# Boris_IO_2.net
KiCad netlist of a schematic drawn in Altium Designer
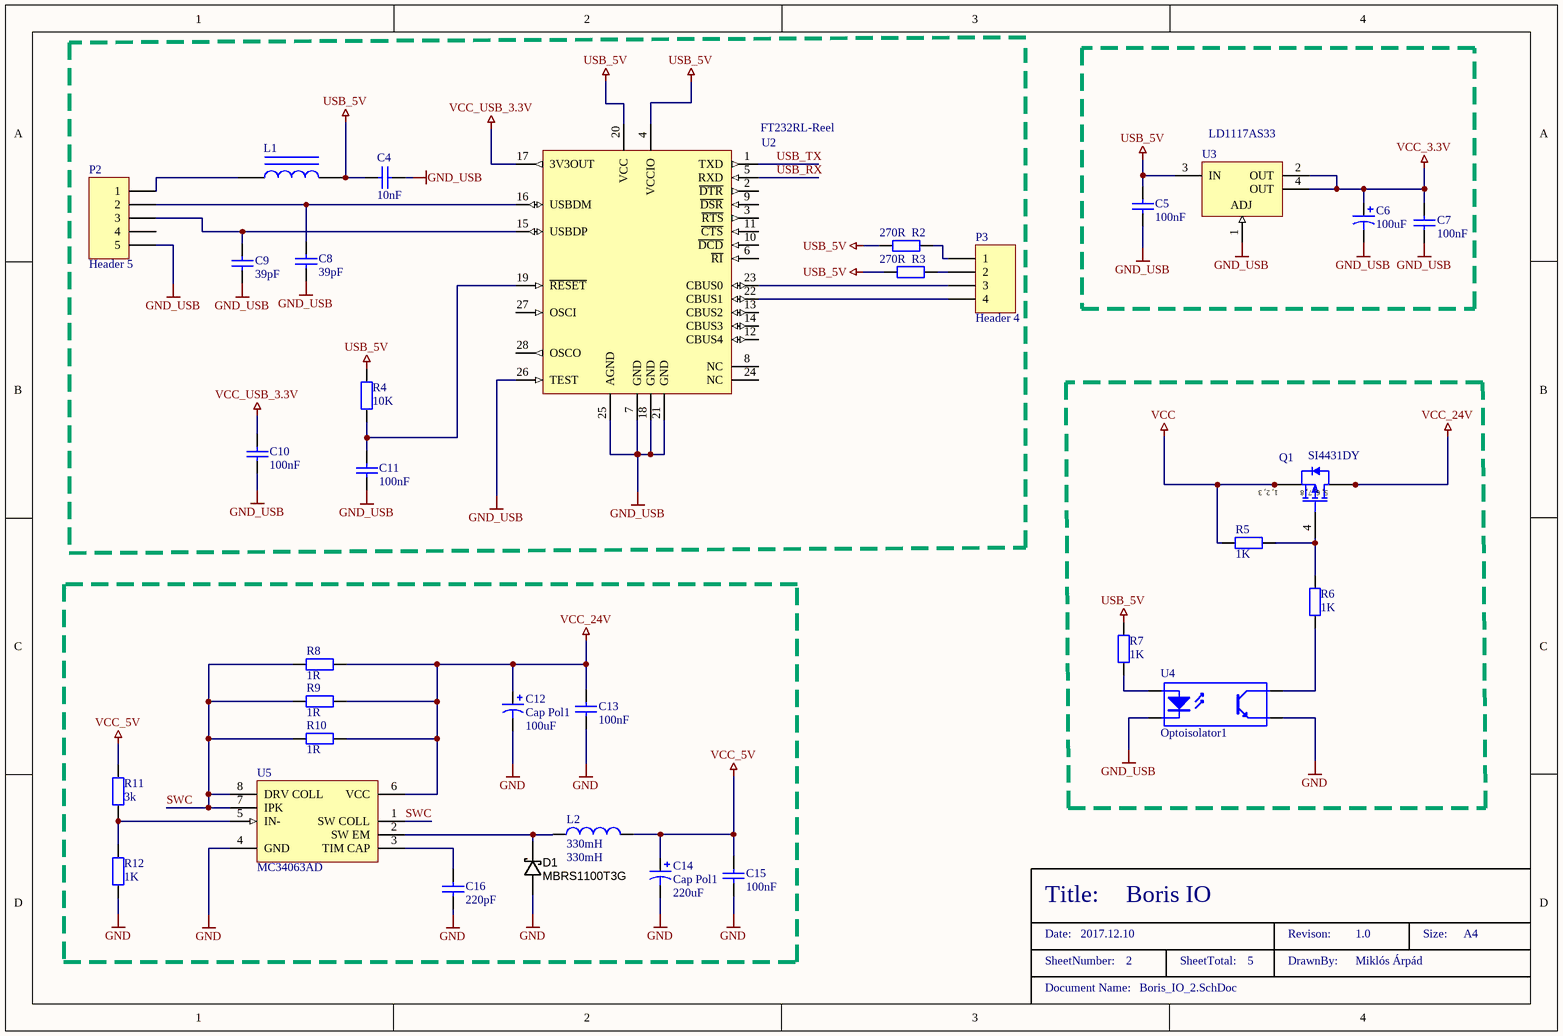
[diagram p0: Boris_IO_2.SchDoc]

(export (version "E")
  (design (tool "Eeschema 10.0.6"))
  (components
    (comp (ref "C4")
      (value "10nF")
      (footprint "0805_CAP")
      (description "Capacitor")
      (libsource (lib "Miscellaneous Devices") (part "Cap"))
    )
    (comp (ref "C5")
      (value "100nF")
      (footprint "0805_CAP")
      (description "Capacitor")
      (libsource (lib "Miscellaneous Devices") (part "Cap"))
    )
    (comp (ref "C6")
      (value "100uF")
      (footprint "7343")
      (description "Polarized Capacitor (Radial)")
      (libsource (lib "MI_SPAZIO") (part "Cap Pol1"))
    )
    (comp (ref "C7")
      (value "100nF")
      (footprint "0805_CAP")
      (description "Capacitor")
      (libsource (lib "Miscellaneous Devices") (part "Cap"))
    )
    (comp (ref "C8")
      (value "39pF")
      (footprint "0805_CAP")
      (description "Capacitor")
      (libsource (lib "Miscellaneous Devices") (part "Cap"))
    )
    (comp (ref "C9")
      (value "39pF")
      (footprint "0805_CAP")
      (description "Capacitor")
      (libsource (lib "Miscellaneous Devices") (part "Cap"))
    )
    (comp (ref "C10")
      (value "100nF")
      (footprint "0805_CAP")
      (description "Capacitor")
      (libsource (lib "Miscellaneous Devices") (part "Cap"))
    )
    (comp (ref "C11")
      (value "100nF")
      (footprint "0805_CAP")
      (description "Capacitor")
      (libsource (lib "Miscellaneous Devices") (part "Cap"))
    )
    (comp (ref "C12")
      (value "Cap Pol1")
      (footprint "CAP_ELEC_SIZE_G")
      (description "Polarized Capacitor (Radial)")
      (fields (field (name "ALTIUM_VALUE") "100uF"))
      (libsource (lib "Miscellaneous Devices") (part "Cap Pol1"))
    )
    (comp (ref "C13")
      (value "100nF")
      (footprint "CAPC3216N")
      (description "Capacitor")
      (libsource (lib "Miscellaneous Devices") (part "Cap"))
    )
    (comp (ref "C14")
      (value "Cap Pol1")
      (footprint "CAP_ELEC_SIZE_E")
      (description "Polarized Capacitor (Radial)")
      (fields (field (name "ALTIUM_VALUE") "220uF"))
      (libsource (lib "Miscellaneous Devices") (part "Cap Pol1"))
    )
    (comp (ref "C15")
      (value "100nF")
      (footprint "CAPC3216N")
      (description "Capacitor")
      (libsource (lib "Miscellaneous Devices") (part "Cap"))
    )
    (comp (ref "C16")
      (value "220pF")
      (footprint "0805_CAP")
      (description "Capacitor")
      (libsource (lib "Miscellaneous Devices") (part "Cap"))
    )
    (comp (ref "D1")
      (value "MBRS1100T3G")
      (footprint "DO-214AA")
      (description "Diode Schottky SMD 30V 1A DO-214AA")
      (libsource (lib "PBL - Diodes") (part "DIODE_SCHOTTKY_MBRS130L"))
    )
    (comp (ref "L1")
      (value "Inductor Iron")
      (footprint "0805_ind")
      (description "Magnetic-Core Inductor")
      (libsource (lib "Miscellaneous Devices") (part "Inductor Iron"))
    )
    (comp (ref "L2")
      (value "330mH")
      (footprint "IND_Coilcraft_DO3316P_SM")
      (description "Inductor")
      (fields (field (name "ALTIUM_VALUE") "330mH"))
      (libsource (lib "Miscellaneous Devices") (part "Inductor"))
    )
    (comp (ref "P2")
      (value "Header 5")
      (footprint "HDR1X5")
      (description "Header, 5-Pin")
      (fields (field (name "PUBLISHER") "Altium Limited"))
      (libsource (lib "Miscellaneous Connectors") (part "Header 5"))
    )
    (comp (ref "P3")
      (value "Header 4")
      (footprint "HDR1X4")
      (description "Header, 4-Pin")
      (fields (field (name "PUBLISHER") "Altium Limited"))
      (libsource (lib "Miscellaneous Connectors") (part "Header 4"))
    )
    (comp (ref "Q1")
      (value "SI4431DY")
      (footprint "SO-8_N")
      (description "P-Channel 30V (D-S)  MOSFET")
      (fields (field (name "PUBLISHER") "Altium Limited"))
      (libsource (lib "Vishay Siliconix Discrete MOSFET") (part "SI4431DY"))
    )
    (comp (ref "R2")
      (value "270R")
      (footprint "0805_RES")
      (description "Resistor")
      (libsource (lib "") (part "Res2_2"))
    )
    (comp (ref "R3")
      (value "270R")
      (footprint "0805_RES")
      (description "Resistor")
      (libsource (lib "") (part "Res2_2"))
    )
    (comp (ref "R4")
      (value "10K")
      (footprint "0805_RES")
      (description "Resistor")
      (libsource (lib "") (part "Res2_3"))
    )
    (comp (ref "R5")
      (value "1K")
      (footprint "RESC3216N")
      (description "Resistor")
      (libsource (lib "") (part "Res2_2"))
    )
    (comp (ref "R6")
      (value "1K")
      (footprint "RESC3216N")
      (description "Resistor")
      (libsource (lib "") (part "Res2_1"))
    )
    (comp (ref "R7")
      (value "1K")
      (footprint "RESC3216N")
      (description "Resistor")
      (libsource (lib "") (part "Res2_1"))
    )
    (comp (ref "R8")
      (value "1R")
      (footprint "RESC3216N")
      (description "Resistor")
      (libsource (lib "Miscellaneous Devices") (part "Res2"))
    )
    (comp (ref "R9")
      (value "1R")
      (footprint "RESC3216N")
      (description "Resistor")
      (libsource (lib "Miscellaneous Devices") (part "Res2"))
    )
    (comp (ref "R10")
      (value "1R")
      (footprint "RESC3216N")
      (description "Resistor")
      (libsource (lib "Miscellaneous Devices") (part "Res2"))
    )
    (comp (ref "R11")
      (value "3k")
      (footprint "RESC3216N")
      (description "Resistor")
      (libsource (lib "") (part "Res2_1"))
    )
    (comp (ref "R12")
      (value "1K")
      (footprint "RESC3216N")
      (description "Resistor")
      (libsource (lib "") (part "Res2_1"))
    )
    (comp (ref "U2")
      (value "FT232RL-Reel")
      (footprint "SSOP-28_N")
      (description "USB UART Asynchronous Serial Data Transfer Chip, SSOP-28, Tape and Reel")
      (libsource (lib "FTDI Communication UART") (part "FT232RL-Reel"))
    )
    (comp (ref "U3")
      (value "LD1117AS33")
      (footprint "318E-04")
      (description "Three-Terminal Adjustable Output Positive Voltage Regulator")
      (libsource (lib "ON Semi Power Mgt Voltage Regulator") (part "LM317MBSTT3"))
    )
    (comp (ref "U4")
      (value "Optoisolator1")
      (footprint "DIP-4")
      (description "4-Pin Phototransistor Optocoupler")
      (fields (field (name "PUBLISHER") "Altium Limited"))
      (libsource (lib "Miscellaneous Devices") (part "Optoisolator1"))
    )
    (comp (ref "U5")
      (value "MC34063AD")
      (footprint "751-05_N")
      (description "DC-to-DC Converter Control Circuit")
      (libsource (lib "ON Semi Power Mgt DC-DC Converter") (part "MC34063AD"))
    )
  )
  (nets
    (net (code "1") (name "/SWC") (class "Default")
      (node (ref "R10") (pin "2") (pinfunction "2_2") (pintype "passive"))
      (node (ref "R8") (pin "2") (pinfunction "2_2") (pintype "passive"))
      (node (ref "R9") (pin "2") (pinfunction "2_2") (pintype "passive"))
      (node (ref "U5") (pin "1") (pinfunction "SW_COLL_1") (pintype "passive"))
      (node (ref "U5") (pin "7") (pinfunction "IPK_7") (pintype "passive"))
      (node (ref "U5") (pin "8") (pinfunction "DRV_COLL_8") (pintype "open_collector"))
    )
    (net (code "2") (name "/USB_RX") (class "Default")
      (node (ref "U2") (pin "5") (pinfunction "RXD_5") (pintype "input"))
    )
    (net (code "3") (name "/USB_TX") (class "Default")
      (node (ref "U2") (pin "1") (pinfunction "TXD_1") (pintype "output"))
    )
    (net (code "4") (name "GND") (class "Default")
      (node (ref "C12") (pin "2") (pinfunction "2_2") (pintype "passive"))
      (node (ref "C13") (pin "2") (pinfunction "2_2") (pintype "passive"))
      (node (ref "C14") (pin "2") (pinfunction "2_2") (pintype "passive"))
      (node (ref "C15") (pin "2") (pinfunction "2_2") (pintype "passive"))
      (node (ref "C16") (pin "2") (pinfunction "2_2") (pintype "passive"))
      (node (ref "D1") (pin "A") (pinfunction "A_A") (pintype "passive"))
      (node (ref "R12") (pin "2") (pinfunction "2_2") (pintype "passive"))
      (node (ref "U4") (pin "3") (pinfunction "E_3") (pintype "passive"))
      (node (ref "U5") (pin "4") (pinfunction "GND_4") (pintype "power_in"))
    )
    (net (code "5") (name "GND_USB") (class "Default")
      (node (ref "C10") (pin "2") (pinfunction "2_2") (pintype "passive"))
      (node (ref "C11") (pin "2") (pinfunction "2_2") (pintype "passive"))
      (node (ref "C4") (pin "2") (pinfunction "2_2") (pintype "passive"))
      (node (ref "C5") (pin "2") (pinfunction "2_2") (pintype "passive"))
      (node (ref "C6") (pin "2") (pinfunction "2_2") (pintype "passive"))
      (node (ref "C7") (pin "2") (pinfunction "2_2") (pintype "passive"))
      (node (ref "C8") (pin "1") (pinfunction "1_1") (pintype "passive"))
      (node (ref "C9") (pin "1") (pinfunction "1_1") (pintype "passive"))
      (node (ref "P2") (pin "5") (pinfunction "5_5") (pintype "passive"))
      (node (ref "U2") (pin "18") (pinfunction "GND_18") (pintype "power_in"))
      (node (ref "U2") (pin "21") (pinfunction "GND_21") (pintype "power_in"))
      (node (ref "U2") (pin "25") (pinfunction "AGND_25") (pintype "power_in"))
      (node (ref "U2") (pin "26") (pinfunction "TEST_26") (pintype "input"))
      (node (ref "U2") (pin "7") (pinfunction "GND_7") (pintype "power_in"))
      (node (ref "U3") (pin "1") (pinfunction "ADJ_1") (pintype "input"))
      (node (ref "U4") (pin "2") (pinfunction "K_2") (pintype "passive"))
    )
    (net (code "6") (name "Net-(L1-Pad1)") (class "Default")
      (node (ref "L1") (pin "1") (pinfunction "1_1") (pintype "passive"))
      (node (ref "P2") (pin "1") (pinfunction "1_1") (pintype "passive"))
    )
    (net (code "7") (name "Net-(P3-Pad1)") (class "Default")
      (node (ref "P3") (pin "1") (pinfunction "1_1") (pintype "passive"))
      (node (ref "R2") (pin "2") (pinfunction "2_2") (pintype "passive"))
    )
    (net (code "8") (name "Net-(P3-Pad2)") (class "Default")
      (node (ref "P3") (pin "2") (pinfunction "2_2") (pintype "passive"))
      (node (ref "R3") (pin "2") (pinfunction "2_2") (pintype "passive"))
    )
    (net (code "9") (name "Net-(Q1-G)") (class "Default")
      (node (ref "Q1") (pin "4") (pinfunction "G_4") (pintype "passive"))
      (node (ref "R5") (pin "2") (pinfunction "2_2") (pintype "passive"))
      (node (ref "R6") (pin "1") (pinfunction "1_1") (pintype "passive"))
    )
    (net (code "10") (name "Net-(U2-CBUS0)") (class "Default")
      (node (ref "P3") (pin "3") (pinfunction "3_3") (pintype "passive"))
      (node (ref "U2") (pin "23") (pinfunction "CBUS0_23") (pintype "bidirectional"))
    )
    (net (code "11") (name "Net-(U2-CBUS1)") (class "Default")
      (node (ref "P3") (pin "4") (pinfunction "4_4") (pintype "passive"))
      (node (ref "U2") (pin "22") (pinfunction "CBUS1_22") (pintype "bidirectional"))
    )
    (net (code "12") (name "Net-(U2-USBDM)") (class "Default")
      (node (ref "C8") (pin "2") (pinfunction "2_2") (pintype "passive"))
      (node (ref "P2") (pin "2") (pinfunction "2_2") (pintype "passive"))
      (node (ref "U2") (pin "16") (pinfunction "USBDM_16") (pintype "bidirectional"))
    )
    (net (code "13") (name "Net-(U2-USBDP)") (class "Default")
      (node (ref "C9") (pin "2") (pinfunction "2_2") (pintype "passive"))
      (node (ref "P2") (pin "3") (pinfunction "3_3") (pintype "passive"))
      (node (ref "U2") (pin "15") (pinfunction "USBDP_15") (pintype "bidirectional"))
    )
    (net (code "14") (name "Net-(U2-~{RESET})") (class "Default")
      (node (ref "C11") (pin "1") (pinfunction "1_1") (pintype "passive"))
      (node (ref "R4") (pin "1") (pinfunction "1_1") (pintype "passive"))
      (node (ref "U2") (pin "19") (pinfunction "~{RESET}_19") (pintype "input"))
    )
    (net (code "15") (name "Net-(U4-A)") (class "Default")
      (node (ref "R7") (pin "2") (pinfunction "2_2") (pintype "passive"))
      (node (ref "U4") (pin "1") (pinfunction "A_1") (pintype "passive"))
    )
    (net (code "16") (name "Net-(U4-C)") (class "Default")
      (node (ref "R6") (pin "2") (pinfunction "2_2") (pintype "passive"))
      (node (ref "U4") (pin "4") (pinfunction "C_4") (pintype "passive"))
    )
    (net (code "17") (name "Net-(U5-IN-)") (class "Default")
      (node (ref "R11") (pin "2") (pinfunction "2_2") (pintype "passive"))
      (node (ref "R12") (pin "1") (pinfunction "1_1") (pintype "passive"))
      (node (ref "U5") (pin "5") (pinfunction "IN-_5") (pintype "input"))
    )
    (net (code "18") (name "Net-(U5-SW_EM)") (class "Default")
      (node (ref "D1") (pin "K") (pinfunction "K_K") (pintype "passive"))
      (node (ref "L2") (pin "1") (pinfunction "1_1") (pintype "passive"))
      (node (ref "U5") (pin "2") (pinfunction "SW_EM_2") (pintype "passive"))
    )
    (net (code "19") (name "Net-(U5-TIM_CAP)") (class "Default")
      (node (ref "C16") (pin "1") (pinfunction "1_1") (pintype "passive"))
      (node (ref "U5") (pin "3") (pinfunction "TIM_CAP_3") (pintype "passive"))
    )
    (net (code "20") (name "USB_5V") (class "Default")
      (node (ref "C4") (pin "1") (pinfunction "1_1") (pintype "passive"))
      (node (ref "C5") (pin "1") (pinfunction "1_1") (pintype "passive"))
      (node (ref "L1") (pin "2") (pinfunction "2_2") (pintype "passive"))
      (node (ref "R2") (pin "1") (pinfunction "1_1") (pintype "passive"))
      (node (ref "R3") (pin "1") (pinfunction "1_1") (pintype "passive"))
      (node (ref "R4") (pin "2") (pinfunction "2_2") (pintype "passive"))
      (node (ref "R7") (pin "1") (pinfunction "1_1") (pintype "passive"))
      (node (ref "U2") (pin "20") (pinfunction "VCC_20") (pintype "power_in"))
      (node (ref "U2") (pin "4") (pinfunction "VCCIO_4") (pintype "power_in"))
      (node (ref "U3") (pin "3") (pinfunction "IN_3") (pintype "power_in"))
    )
    (net (code "21") (name "VCC") (class "Default")
      (node (ref "Q1") (pin "1") (pinfunction "S_1") (pintype "passive"))
      (node (ref "Q1") (pin "2") (pinfunction "S_2") (pintype "passive"))
      (node (ref "Q1") (pin "3") (pinfunction "S_3") (pintype "passive"))
      (node (ref "R5") (pin "1") (pinfunction "1_1") (pintype "passive"))
    )
    (net (code "22") (name "VCC_3.3V") (class "Default")
      (node (ref "C6") (pin "1") (pinfunction "1_1") (pintype "passive"))
      (node (ref "C7") (pin "1") (pinfunction "1_1") (pintype "passive"))
      (node (ref "U3") (pin "2") (pinfunction "OUT_2") (pintype "power_in"))
      (node (ref "U3") (pin "4") (pinfunction "OUT_4") (pintype "power_in"))
    )
    (net (code "23") (name "VCC_5V") (class "Default")
      (node (ref "C14") (pin "1") (pinfunction "1_1") (pintype "passive"))
      (node (ref "C15") (pin "1") (pinfunction "1_1") (pintype "passive"))
      (node (ref "L2") (pin "2") (pinfunction "2_2") (pintype "passive"))
      (node (ref "R11") (pin "1") (pinfunction "1_1") (pintype "passive"))
    )
    (net (code "24") (name "VCC_24V") (class "Default")
      (node (ref "C12") (pin "1") (pinfunction "1_1") (pintype "passive"))
      (node (ref "C13") (pin "1") (pinfunction "1_1") (pintype "passive"))
      (node (ref "Q1") (pin "5") (pinfunction "D_5") (pintype "passive"))
      (node (ref "Q1") (pin "6") (pinfunction "D_6") (pintype "passive"))
      (node (ref "Q1") (pin "7") (pinfunction "D_7") (pintype "passive"))
      (node (ref "Q1") (pin "8") (pinfunction "D_8") (pintype "passive"))
      (node (ref "R10") (pin "1") (pinfunction "1_1") (pintype "passive"))
      (node (ref "R8") (pin "1") (pinfunction "1_1") (pintype "passive"))
      (node (ref "R9") (pin "1") (pinfunction "1_1") (pintype "passive"))
      (node (ref "U5") (pin "6") (pinfunction "VCC_6") (pintype "power_in"))
    )
    (net (code "25") (name "VCC_USB_3.3V") (class "Default")
      (node (ref "C10") (pin "1") (pinfunction "1_1") (pintype "passive"))
      (node (ref "U2") (pin "17") (pinfunction "3V3OUT_17") (pintype "output"))
    )
    (net (code "26") (name "unconnected-(P2-Pad4)") (class "Default")
      (node (ref "P2") (pin "4") (pinfunction "4_4") (pintype "passive"))
    )
    (net (code "27") (name "unconnected-(U2-CBUS2-Pad13)") (class "Default")
      (node (ref "U2") (pin "13") (pinfunction "CBUS2_13") (pintype "bidirectional"))
    )
    (net (code "28") (name "unconnected-(U2-CBUS3-Pad14)") (class "Default")
      (node (ref "U2") (pin "14") (pinfunction "CBUS3_14") (pintype "bidirectional"))
    )
    (net (code "29") (name "unconnected-(U2-CBUS4-Pad12)") (class "Default")
      (node (ref "U2") (pin "12") (pinfunction "CBUS4_12") (pintype "bidirectional"))
    )
    (net (code "30") (name "unconnected-(U2-NC-Pad8)") (class "Default")
      (node (ref "U2") (pin "8") (pinfunction "NC_8") (pintype "passive"))
    )
    (net (code "31") (name "unconnected-(U2-NC-Pad24)") (class "Default")
      (node (ref "U2") (pin "24") (pinfunction "NC_24") (pintype "passive"))
    )
    (net (code "32") (name "unconnected-(U2-OSCI-Pad27)") (class "Default")
      (node (ref "U2") (pin "27") (pinfunction "OSCI_27") (pintype "input"))
    )
    (net (code "33") (name "unconnected-(U2-OSCO-Pad28)") (class "Default")
      (node (ref "U2") (pin "28") (pinfunction "OSCO_28") (pintype "output"))
    )
    (net (code "34") (name "unconnected-(U2-~{CTS}-Pad11)") (class "Default")
      (node (ref "U2") (pin "11") (pinfunction "~{CTS}_11") (pintype "input"))
    )
    (net (code "35") (name "unconnected-(U2-~{DCD}-Pad10)") (class "Default")
      (node (ref "U2") (pin "10") (pinfunction "~{DCD}_10") (pintype "input"))
    )
    (net (code "36") (name "unconnected-(U2-~{DSR}-Pad9)") (class "Default")
      (node (ref "U2") (pin "9") (pinfunction "~{DSR}_9") (pintype "input"))
    )
    (net (code "37") (name "unconnected-(U2-~{DTR}-Pad2)") (class "Default")
      (node (ref "U2") (pin "2") (pinfunction "~{DTR}_2") (pintype "output"))
    )
    (net (code "38") (name "unconnected-(U2-~{RI}-Pad6)") (class "Default")
      (node (ref "U2") (pin "6") (pinfunction "~{RI}_6") (pintype "input"))
    )
    (net (code "39") (name "unconnected-(U2-~{RTS}-Pad3)") (class "Default")
      (node (ref "U2") (pin "3") (pinfunction "~{RTS}_3") (pintype "output"))
    )
  )
)
